# v1_board.net
KiCad netlist of a schematic drawn in EAGLE
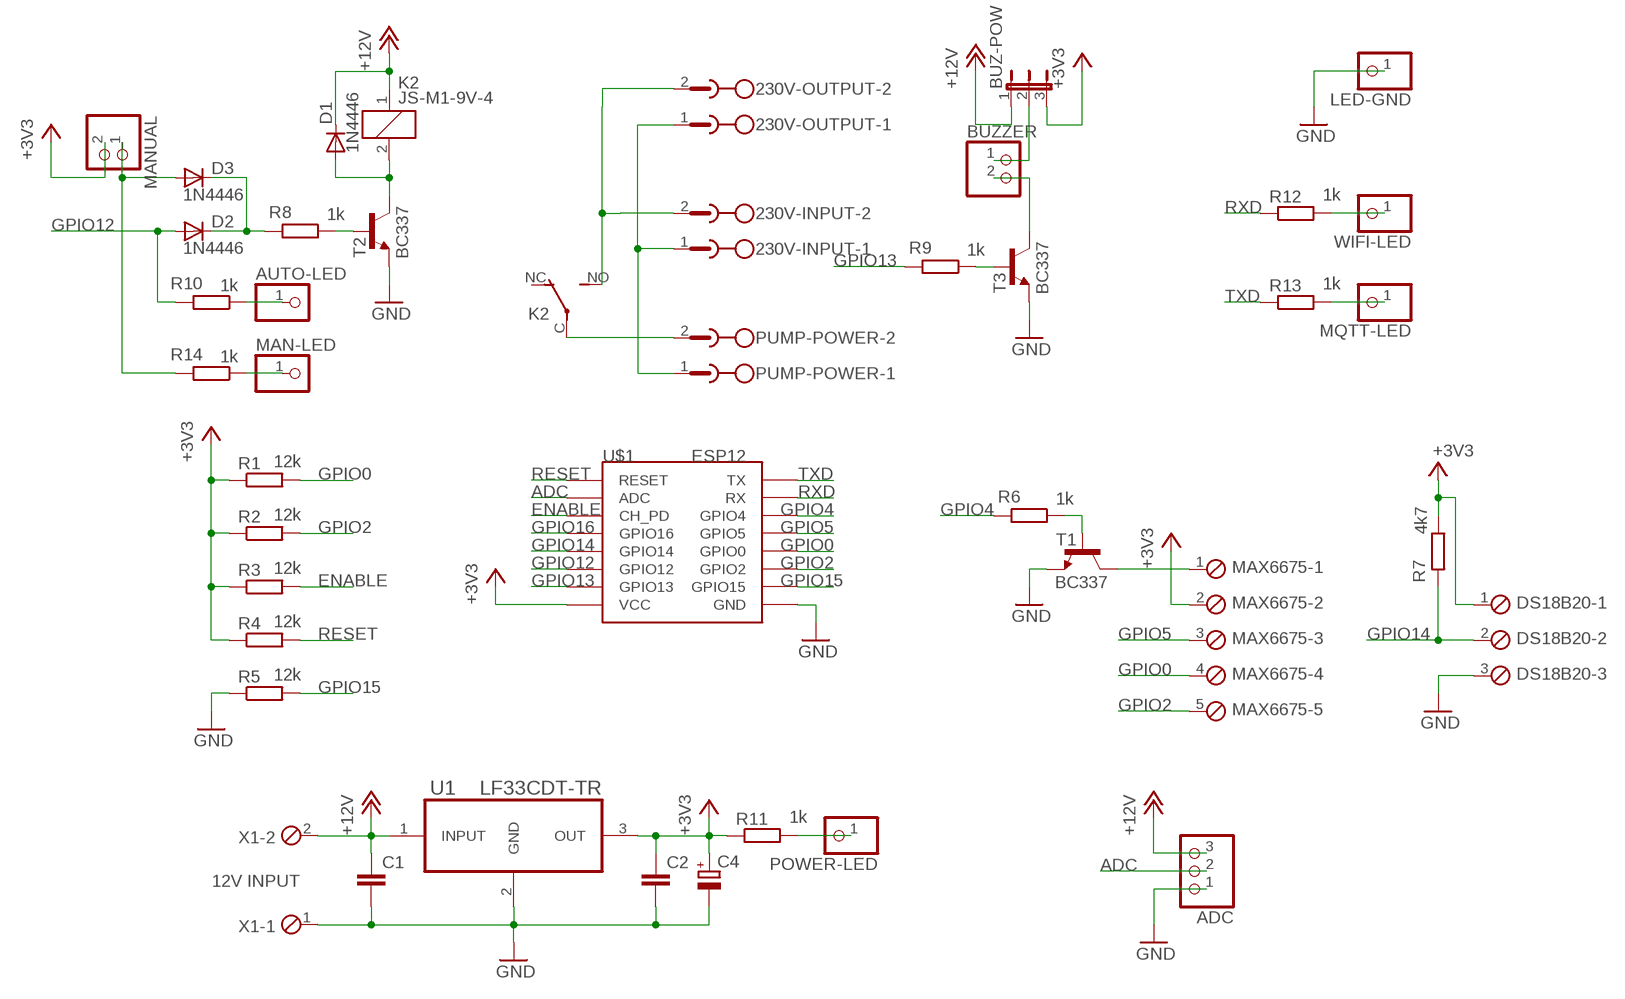
[diagram p0: schematic, sheet 1]

(export (version "E")
  (design (tool "Eeschema 10.0.6"))
  (components
    (comp (ref "230V-INPUT")
      (value "MSTBV2")
      (footprint "eagle-import:MSTBV2")
      (fields (field (name "MPN") "MSTBV 2,5/2-GF-5.08"))
      (libsource (lib "eagle-import") (part "MSTBV2"))
    )
    (comp (ref "230V-OUTPUT")
      (value "MSTBV2")
      (footprint "eagle-import:MSTBV2")
      (fields (field (name "MPN") "MSTBV 2,5/2-GF-5.08"))
      (libsource (lib "eagle-import") (part "MSTBV2"))
    )
    (comp (ref "ADC")
      (value "PINHD-1X3")
      (footprint "eagle-import:1X03")
      (libsource (lib "eagle-import") (part "PINHD-1X3"))
    )
    (comp (ref "AUTO-LED")
      (value "PINHD-1X1")
      (footprint "eagle-import:1X01")
      (libsource (lib "eagle-import") (part "PINHD-1X1"))
    )
    (comp (ref "BUZ-POW")
      (value "JP2E")
      (footprint "eagle-import:JP2")
      (libsource (lib "eagle-import") (part "JP2E"))
    )
    (comp (ref "BUZZER")
      (value "PINHD-1X2")
      (footprint "eagle-import:1X02")
      (libsource (lib "eagle-import") (part "PINHD-1X2"))
    )
    (comp (ref "C1")
      (value "C-EU025-025X050")
      (footprint "eagle-import:C025-025X050")
      (libsource (lib "eagle-import") (part "C-EU025-025X050"))
    )
    (comp (ref "C2")
      (value "C-EU025-025X050")
      (footprint "eagle-import:C025-025X050")
      (libsource (lib "eagle-import") (part "C-EU025-025X050"))
    )
    (comp (ref "C4")
      (value "CPOL-EUE3.5-8")
      (footprint "eagle-import:E3,5-8")
      (libsource (lib "eagle-import") (part "CPOL-EUE3.5-8"))
    )
    (comp (ref "D1")
      (value "1N4446")
      (footprint "eagle-import:DO35-10")
      (libsource (lib "eagle-import") (part "1N4446"))
    )
    (comp (ref "D2")
      (value "1N4446")
      (footprint "eagle-import:DO35-10")
      (libsource (lib "eagle-import") (part "1N4446"))
    )
    (comp (ref "D3")
      (value "1N4446")
      (footprint "eagle-import:DO35-10")
      (libsource (lib "eagle-import") (part "1N4446"))
    )
    (comp (ref "DS18B20")
      (value "MPT3")
      (footprint "eagle-import:3POL254")
      (libsource (lib "eagle-import") (part "MPT3"))
    )
    (comp (ref "K2")
      (value "JS-M1-9V-4")
      (footprint "eagle-import:JS-M")
      (libsource (lib "eagle-import") (part "JS-M1-9V-4"))
    )
    (comp (ref "LED-GND")
      (value "PINHD-1X1")
      (footprint "eagle-import:1X01")
      (libsource (lib "eagle-import") (part "PINHD-1X1"))
    )
    (comp (ref "MAN-LED")
      (value "PINHD-1X1")
      (footprint "eagle-import:1X01")
      (libsource (lib "eagle-import") (part "PINHD-1X1"))
    )
    (comp (ref "MANUAL")
      (value "PINHD-1X2")
      (footprint "eagle-import:1X02")
      (libsource (lib "eagle-import") (part "PINHD-1X2"))
    )
    (comp (ref "MAX6675")
      (value "MPT5")
      (footprint "eagle-import:5POL254")
      (libsource (lib "eagle-import") (part "MPT5"))
    )
    (comp (ref "MQTT-LED")
      (value "PINHD-1X1")
      (footprint "eagle-import:1X01")
      (libsource (lib "eagle-import") (part "PINHD-1X1"))
    )
    (comp (ref "POWER-LED")
      (value "PINHD-1X1")
      (footprint "eagle-import:1X01")
      (libsource (lib "eagle-import") (part "PINHD-1X1"))
    )
    (comp (ref "PUMP-POWER")
      (value "MSTBV2")
      (footprint "eagle-import:MSTBV2")
      (fields (field (name "MPN") "MSTBV 2,5/2-GF-5.08"))
      (libsource (lib "eagle-import") (part "MSTBV2"))
    )
    (comp (ref "R1")
      (value "12k")
      (footprint "eagle-import:R1206")
      (libsource (lib "eagle-import") (part "R-EU_R1206"))
    )
    (comp (ref "R2")
      (value "12k")
      (footprint "eagle-import:R1206")
      (libsource (lib "eagle-import") (part "R-EU_R1206"))
    )
    (comp (ref "R3")
      (value "12k")
      (footprint "eagle-import:R1206")
      (libsource (lib "eagle-import") (part "R-EU_R1206"))
    )
    (comp (ref "R4")
      (value "12k")
      (footprint "eagle-import:R1206")
      (libsource (lib "eagle-import") (part "R-EU_R1206"))
    )
    (comp (ref "R5")
      (value "12k")
      (footprint "eagle-import:R1206")
      (libsource (lib "eagle-import") (part "R-EU_R1206"))
    )
    (comp (ref "R6")
      (value "1k")
      (footprint "eagle-import:R1206")
      (libsource (lib "eagle-import") (part "R-EU_R1206"))
    )
    (comp (ref "R7")
      (value "4k7")
      (footprint "eagle-import:R1206")
      (libsource (lib "eagle-import") (part "R-EU_R1206"))
    )
    (comp (ref "R8")
      (value "1k")
      (footprint "eagle-import:R1206")
      (libsource (lib "eagle-import") (part "R-EU_R1206"))
    )
    (comp (ref "R9")
      (value "1k")
      (footprint "eagle-import:R1206")
      (libsource (lib "eagle-import") (part "R-EU_R1206"))
    )
    (comp (ref "R10")
      (value "1k")
      (footprint "eagle-import:R1206")
      (libsource (lib "eagle-import") (part "R-EU_R1206"))
    )
    (comp (ref "R11")
      (value "1k")
      (footprint "eagle-import:R1206")
      (libsource (lib "eagle-import") (part "R-EU_R1206"))
    )
    (comp (ref "R12")
      (value "1k")
      (footprint "eagle-import:R1206")
      (libsource (lib "eagle-import") (part "R-EU_R1206"))
    )
    (comp (ref "R13")
      (value "1k")
      (footprint "eagle-import:R1206")
      (libsource (lib "eagle-import") (part "R-EU_R1206"))
    )
    (comp (ref "R14")
      (value "1k")
      (footprint "eagle-import:R1206")
      (libsource (lib "eagle-import") (part "R-EU_R1206"))
    )
    (comp (ref "T1")
      (value "BC337")
      (footprint "eagle-import:TO92")
      (libsource (lib "eagle-import") (part "BC337"))
    )
    (comp (ref "T2")
      (value "BC337")
      (footprint "eagle-import:TO92")
      (libsource (lib "eagle-import") (part "BC337"))
    )
    (comp (ref "T3")
      (value "BC337")
      (footprint "eagle-import:TO92")
      (libsource (lib "eagle-import") (part "BC337"))
    )
    (comp (ref "U$1")
      (value "ESP12")
      (footprint "eagle-import:ESP12")
      (libsource (lib "eagle-import") (part "ESP12"))
    )
    (comp (ref "U1")
      (value "LF33CDT-TR")
      (footprint "eagle-import:TO228P972X240-3N")
      (fields (field (name "MF") "STMicroelectronics"))
      (libsource (lib "eagle-import") (part "LF33CDT-TR"))
    )
    (comp (ref "WIFI-LED")
      (value "PINHD-1X1")
      (footprint "eagle-import:1X01")
      (libsource (lib "eagle-import") (part "PINHD-1X1"))
    )
    (comp (ref "X1")
      (value "12V INPUT")
      (footprint "eagle-import:2POL254")
      (libsource (lib "eagle-import") (part "MPT2"))
    )
  )
  (nets
    (net (code "1") (name "+3V3") (class "Default")
      (node (ref "BUZ-POW") (pin "3") (pinfunction "3_3") (pintype "passive"))
      (node (ref "C2") (pin "1") (pinfunction "1_1") (pintype "passive"))
      (node (ref "C4") (pin "+") (pinfunction "+_+") (pintype "passive"))
      (node (ref "DS18B20") (pin "1") (pinfunction "1_1") (pintype "passive"))
      (node (ref "MANUAL") (pin "2") (pinfunction "2_2") (pintype "passive"))
      (node (ref "MAX6675") (pin "2") (pinfunction "1_2") (pintype "passive"))
      (node (ref "R1") (pin "1") (pinfunction "1_1") (pintype "passive"))
      (node (ref "R11") (pin "1") (pinfunction "1_1") (pintype "passive"))
      (node (ref "R2") (pin "1") (pinfunction "1_1") (pintype "passive"))
      (node (ref "R3") (pin "1") (pinfunction "1_1") (pintype "passive"))
      (node (ref "R4") (pin "1") (pinfunction "1_1") (pintype "passive"))
      (node (ref "R7") (pin "1") (pinfunction "1_1") (pintype "passive"))
      (node (ref "U$1") (pin "VCC") (pinfunction "VCC_VCC") (pintype "bidirectional"))
      (node (ref "U1") (pin "3") (pinfunction "OUT_3") (pintype "output"))
    )
    (net (code "2") (name "+12V") (class "Default")
      (node (ref "ADC") (pin "3") (pinfunction "3_3") (pintype "passive"))
      (node (ref "BUZ-POW") (pin "1") (pinfunction "1_1") (pintype "passive"))
      (node (ref "C1") (pin "1") (pinfunction "1_1") (pintype "passive"))
      (node (ref "D1") (pin "C") (pinfunction "C_C") (pintype "passive"))
      (node (ref "K2") (pin "1") (pinfunction "1_1") (pintype "passive"))
      (node (ref "U1") (pin "1") (pinfunction "INPUT_1") (pintype "input"))
      (node (ref "X1") (pin "2") (pinfunction "1_2") (pintype "passive"))
    )
    (net (code "3") (name "/ADC") (class "Default")
      (node (ref "ADC") (pin "2") (pinfunction "2_2") (pintype "passive"))
      (node (ref "U$1") (pin "ADC") (pinfunction "ADC_ADC") (pintype "bidirectional"))
    )
    (net (code "4") (name "/ENABLE") (class "Default")
      (node (ref "R3") (pin "2") (pinfunction "2_2") (pintype "passive"))
      (node (ref "U$1") (pin "CH_PD") (pinfunction "CH_PD_CH_PD") (pintype "bidirectional"))
    )
    (net (code "5") (name "/GPIO0") (class "Default")
      (node (ref "MAX6675") (pin "4") (pinfunction "1_4") (pintype "passive"))
      (node (ref "R1") (pin "2") (pinfunction "2_2") (pintype "passive"))
      (node (ref "U$1") (pin "GPIO0") (pinfunction "GPIO0_GPIO0") (pintype "bidirectional"))
    )
    (net (code "6") (name "/GPIO2") (class "Default")
      (node (ref "MAX6675") (pin "5") (pinfunction "1_5") (pintype "passive"))
      (node (ref "R2") (pin "2") (pinfunction "2_2") (pintype "passive"))
      (node (ref "U$1") (pin "GPIO2") (pinfunction "GPIO2_GPIO2") (pintype "bidirectional"))
    )
    (net (code "7") (name "/GPIO4") (class "Default")
      (node (ref "R6") (pin "2") (pinfunction "2_2") (pintype "passive"))
      (node (ref "U$1") (pin "GPIO4") (pinfunction "GPIO4_GPIO4") (pintype "bidirectional"))
    )
    (net (code "8") (name "/GPIO5") (class "Default")
      (node (ref "MAX6675") (pin "3") (pinfunction "1_3") (pintype "passive"))
      (node (ref "U$1") (pin "GPIO5") (pinfunction "GPIO5_GPIO5") (pintype "bidirectional"))
    )
    (net (code "9") (name "/GPIO12") (class "Default")
      (node (ref "D2") (pin "A") (pinfunction "A_A") (pintype "passive"))
      (node (ref "R10") (pin "2") (pinfunction "2_2") (pintype "passive"))
      (node (ref "U$1") (pin "GPIO12") (pinfunction "GPIO12_GPIO12") (pintype "bidirectional"))
    )
    (net (code "10") (name "/GPIO13") (class "Default")
      (node (ref "R9") (pin "2") (pinfunction "2_2") (pintype "passive"))
      (node (ref "U$1") (pin "GPIO13") (pinfunction "GPIO13_GPIO13") (pintype "bidirectional"))
    )
    (net (code "11") (name "/GPIO14") (class "Default")
      (node (ref "DS18B20") (pin "2") (pinfunction "1_2") (pintype "passive"))
      (node (ref "R7") (pin "2") (pinfunction "2_2") (pintype "passive"))
      (node (ref "U$1") (pin "GPIO14") (pinfunction "GPIO14_GPIO14") (pintype "bidirectional"))
    )
    (net (code "12") (name "/GPIO15") (class "Default")
      (node (ref "R5") (pin "2") (pinfunction "2_2") (pintype "passive"))
      (node (ref "U$1") (pin "GPIO15") (pinfunction "GPIO15_GPIO15") (pintype "bidirectional"))
    )
    (net (code "13") (name "/GPIO16") (class "Default")
      (node (ref "U$1") (pin "GPIO16") (pinfunction "GPIO16_GPIO16") (pintype "bidirectional"))
    )
    (net (code "14") (name "/RESET") (class "Default")
      (node (ref "R4") (pin "2") (pinfunction "2_2") (pintype "passive"))
      (node (ref "U$1") (pin "RESET") (pinfunction "RESET_RESET") (pintype "bidirectional"))
    )
    (net (code "15") (name "/RXD") (class "Default")
      (node (ref "R12") (pin "1") (pinfunction "1_1") (pintype "passive"))
      (node (ref "U$1") (pin "RX") (pinfunction "RX_RX") (pintype "bidirectional"))
    )
    (net (code "16") (name "/TXD") (class "Default")
      (node (ref "R13") (pin "1") (pinfunction "1_1") (pintype "passive"))
      (node (ref "U$1") (pin "TX") (pinfunction "TX_TX") (pintype "bidirectional"))
    )
    (net (code "17") (name "GND") (class "Default")
      (node (ref "ADC") (pin "1") (pinfunction "1_1") (pintype "passive"))
      (node (ref "C1") (pin "2") (pinfunction "2_2") (pintype "passive"))
      (node (ref "C2") (pin "2") (pinfunction "2_2") (pintype "passive"))
      (node (ref "C4") (pin "-") (pinfunction "-_-") (pintype "passive"))
      (node (ref "DS18B20") (pin "3") (pinfunction "1_3") (pintype "passive"))
      (node (ref "LED-GND") (pin "1") (pinfunction "1_1") (pintype "passive"))
      (node (ref "R5") (pin "1") (pinfunction "1_1") (pintype "passive"))
      (node (ref "T1") (pin "1") (pinfunction "E_1") (pintype "passive"))
      (node (ref "T2") (pin "1") (pinfunction "E_1") (pintype "passive"))
      (node (ref "T3") (pin "1") (pinfunction "E_1") (pintype "passive"))
      (node (ref "U$1") (pin "GND") (pinfunction "GND_GND") (pintype "bidirectional"))
      (node (ref "U1") (pin "2") (pinfunction "GND_2") (pintype "passive"))
      (node (ref "X1") (pin "1") (pinfunction "1_1") (pintype "passive"))
    )
    (net (code "18") (name "Net-(230V-INPUT-Pad1)") (class "Default")
      (node (ref "230V-INPUT") (pin "1") (pinfunction "1_1") (pintype "passive"))
      (node (ref "230V-OUTPUT") (pin "1") (pinfunction "1_1") (pintype "passive"))
      (node (ref "PUMP-POWER") (pin "1") (pinfunction "1_1") (pintype "passive"))
    )
    (net (code "19") (name "Net-(230V-INPUTB-1)") (class "Default")
      (node (ref "230V-INPUT") (pin "2") (pinfunction "1_2") (pintype "passive"))
      (node (ref "230V-OUTPUT") (pin "2") (pinfunction "1_2") (pintype "passive"))
      (node (ref "K2") (pin "NO") (pinfunction "S_NO") (pintype "passive"))
    )
    (net (code "20") (name "Net-(AUTO-LED-Pad1)") (class "Default")
      (node (ref "AUTO-LED") (pin "1") (pinfunction "1_1") (pintype "passive"))
      (node (ref "R10") (pin "1") (pinfunction "1_1") (pintype "passive"))
    )
    (net (code "21") (name "Net-(BUZ-POW-Pad2)") (class "Default")
      (node (ref "BUZ-POW") (pin "2") (pinfunction "2_2") (pintype "passive"))
      (node (ref "BUZZER") (pin "1") (pinfunction "1_1") (pintype "passive"))
    )
    (net (code "22") (name "Net-(D2-PadC)") (class "Default")
      (node (ref "D2") (pin "C") (pinfunction "C_C") (pintype "passive"))
      (node (ref "D3") (pin "C") (pinfunction "C_C") (pintype "passive"))
      (node (ref "R8") (pin "2") (pinfunction "2_2") (pintype "passive"))
    )
    (net (code "23") (name "Net-(D3-PadA)") (class "Default")
      (node (ref "D3") (pin "A") (pinfunction "A_A") (pintype "passive"))
      (node (ref "MANUAL") (pin "1") (pinfunction "1_1") (pintype "passive"))
      (node (ref "R14") (pin "2") (pinfunction "2_2") (pintype "passive"))
    )
    (net (code "24") (name "Net-(K2B-P)") (class "Default")
      (node (ref "K2") (pin "C") (pinfunction "P_C") (pintype "passive"))
      (node (ref "PUMP-POWER") (pin "2") (pinfunction "1_2") (pintype "passive"))
    )
    (net (code "25") (name "Net-(MAN-LED-Pad1)") (class "Default")
      (node (ref "MAN-LED") (pin "1") (pinfunction "1_1") (pintype "passive"))
      (node (ref "R14") (pin "1") (pinfunction "1_1") (pintype "passive"))
    )
    (net (code "26") (name "Net-(MQTT-LED-Pad1)") (class "Default")
      (node (ref "MQTT-LED") (pin "1") (pinfunction "1_1") (pintype "passive"))
      (node (ref "R13") (pin "2") (pinfunction "2_2") (pintype "passive"))
    )
    (net (code "27") (name "Net-(POWER-LED-Pad1)") (class "Default")
      (node (ref "POWER-LED") (pin "1") (pinfunction "1_1") (pintype "passive"))
      (node (ref "R11") (pin "2") (pinfunction "2_2") (pintype "passive"))
    )
    (net (code "28") (name "Net-(R12-Pad2)") (class "Default")
      (node (ref "R12") (pin "2") (pinfunction "2_2") (pintype "passive"))
      (node (ref "WIFI-LED") (pin "1") (pinfunction "1_1") (pintype "passive"))
    )
    (net (code "29") (name "Net-(T1-B)") (class "Default")
      (node (ref "R6") (pin "1") (pinfunction "1_1") (pintype "passive"))
      (node (ref "T1") (pin "2") (pinfunction "B_2") (pintype "passive"))
    )
    (net (code "30") (name "Net-(T1-C)") (class "Default")
      (node (ref "MAX6675") (pin "1") (pinfunction "1_1") (pintype "passive"))
      (node (ref "T1") (pin "3") (pinfunction "C_3") (pintype "passive"))
    )
    (net (code "31") (name "Net-(T2-B)") (class "Default")
      (node (ref "R8") (pin "1") (pinfunction "1_1") (pintype "passive"))
      (node (ref "T2") (pin "2") (pinfunction "B_2") (pintype "passive"))
    )
    (net (code "32") (name "Net-(T2-C)") (class "Default")
      (node (ref "D1") (pin "A") (pinfunction "A_A") (pintype "passive"))
      (node (ref "K2") (pin "2") (pinfunction "2_2") (pintype "passive"))
      (node (ref "T2") (pin "3") (pinfunction "C_3") (pintype "passive"))
    )
    (net (code "33") (name "Net-(T3-B)") (class "Default")
      (node (ref "R9") (pin "1") (pinfunction "1_1") (pintype "passive"))
      (node (ref "T3") (pin "2") (pinfunction "B_2") (pintype "passive"))
    )
    (net (code "34") (name "Net-(T3-C)") (class "Default")
      (node (ref "BUZZER") (pin "2") (pinfunction "2_2") (pintype "passive"))
      (node (ref "T3") (pin "3") (pinfunction "C_3") (pintype "passive"))
    )
    (net (code "35") (name "unconnected-(K2B-O-PadNC)") (class "Default")
      (node (ref "K2") (pin "NC") (pinfunction "O_NC") (pintype "passive"))
    )
  )
)
